# Optical_TX.net
KiCad netlist of a schematic drawn in Altium Designer
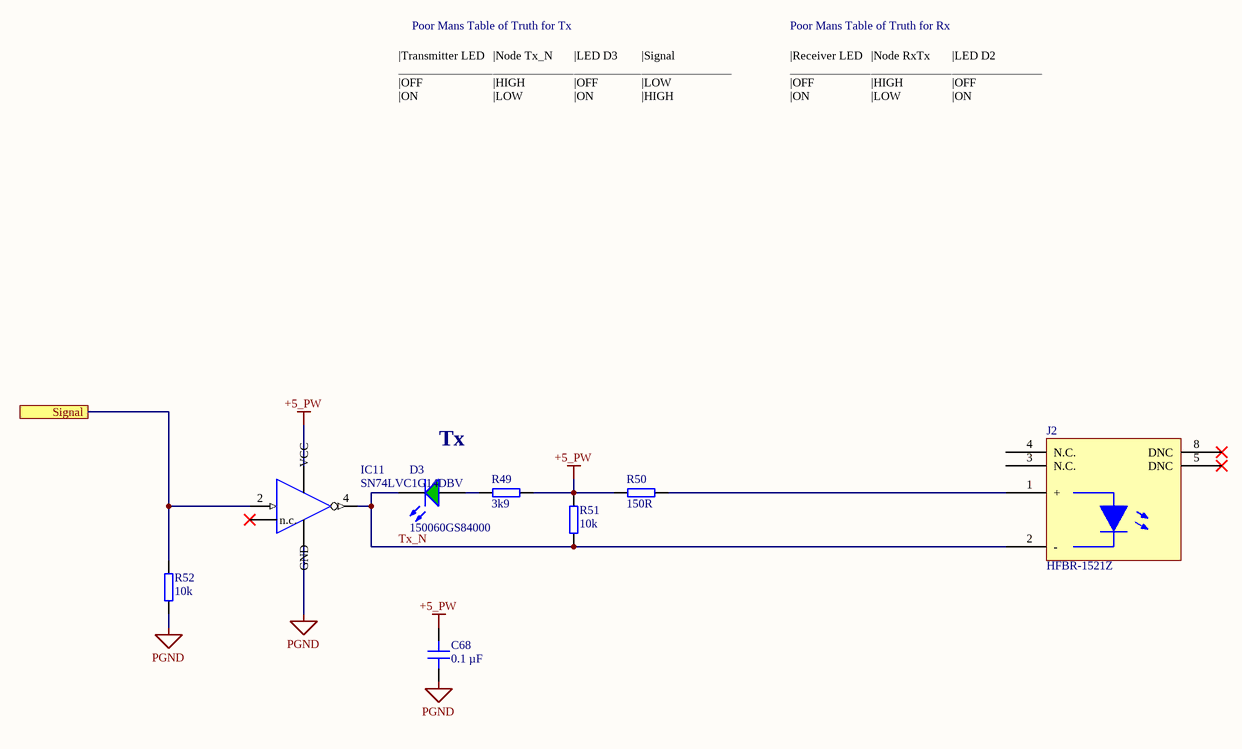
[diagram p0: Optical_TX.SchDoc]

(export (version "E")
  (design (tool "Eeschema 10.0.6"))
  (components
    (comp (ref "C68")
      (value "0.1 µF")
      (footprint "C_0603")
      (description "Capacitor 0603, 50 VDC, 0.1 µF, X7R")
      (fields
        (field (name "MANUFACTURER PART NUMBER") "C0603X104K5RAC7411")
        (field (name "MANUFACTURER") "KEMET")
        (field (name "CREATED FROM") "MGremer")
      )
      (libsource (lib "user") (part "Capacitor"))
    )
    (comp (ref "D3")
      (value "150060GS84000")
      (footprint "WL-SMCW_0603")
      (description "WL-SMCW SMD Mono-color Chip LED Waterclear Green")
      (fields (field (name "MANUFACTURER") "Wuerth Elektronik") (field (name "CREATED FROM") "MGremer"))
      (libsource (lib "user") (part "LED_Green"))
    )
    (comp (ref "IC11")
      (value "SN74LVC1G14DBV")
      (footprint "SOT23-5_L")
      (description "Inverting Schmitt trigger")
      (fields
        (field (name "MANUFACTURER") "Texas Instruments")
        (field (name "LCSC PART NUMBER") "C434069")
        (field (name "CREATED FROM") "VStarost")
      )
      (libsource (lib "user") (part "74AHCX1G14-5"))
    )
    (comp (ref "J2")
      (value "HFBR-1521Z")
      (footprint "HFBRx5XX")
      (description "Fibre Optic Transmitters, Link Horiz 5MBd Tx RoHS")
      (fields
        (field (name "MF") "Broadcom/Avago")
        (field (name "MANUFACTURER") "Broadcom")
        (field (name "CREATED") "2019_04_09_Kreppel")
        (field (name "CREATED FROM") "VStarost")
      )
      (libsource (lib "user") (part "HFBR-1521Z"))
    )
    (comp (ref "R49")
      (value "3k9")
      (footprint "RES 0603_1608")
      (description "SMD resistor E24 series")
      (fields
        (field (name "MANUFACTURER PART NUMBER") "RK73B1JTTDD392J")
        (field (name "MANUFACTURER") "KOA Speer")
        (field (name "CREATED FROM") "MGremer")
      )
      (libsource (lib "user") (part "Resistor"))
    )
    (comp (ref "R50")
      (value "150R")
      (footprint "RES 0603_1608")
      (description "SMD resistor E24 series")
      (fields
        (field (name "MANUFACTURER PART NUMBER") "RK73B1JTTD151J")
        (field (name "MANUFACTURER") "KOA Speer")
        (field (name "CREATED FROM") "MGremer")
      )
      (libsource (lib "user") (part "Resistor"))
    )
    (comp (ref "R51")
      (value "10k")
      (footprint "RES 0603_1608")
      (description "SMD resistor E24 series")
      (fields
        (field (name "MANUFACTURER PART NUMBER") "RK73B1JTTD103J")
        (field (name "MANUFACTURER") "KOA Speer")
        (field (name "CREATED FROM") "MGremer")
      )
      (libsource (lib "user") (part "Resistor"))
    )
    (comp (ref "R52")
      (value "10k")
      (footprint "RES 0603_1608")
      (description "SMD resistor E24 series")
      (fields
        (field (name "MANUFACTURER PART NUMBER") "RK73B1JTTD103J")
        (field (name "MANUFACTURER") "KOA Speer")
        (field (name "CREATED FROM") "MGremer")
      )
      (libsource (lib "user") (part "Resistor"))
    )
  )
  (nets
    (net (code "1") (name "+5_PW") (class "Default")
      (node (ref "C68") (pin "2") (pinfunction "2_2") (pintype "passive"))
      (node (ref "IC11") (pin "5") (pinfunction "VCC_5") (pintype "power_in"))
      (node (ref "R49") (pin "2") (pinfunction "2_2") (pintype "passive"))
      (node (ref "R50") (pin "1") (pinfunction "1_1") (pintype "passive"))
      (node (ref "R51") (pin "2") (pinfunction "2_2") (pintype "passive"))
    )
    (net (code "2") (name "/Signal") (class "Default")
      (node (ref "IC11") (pin "2") (pinfunction "A_2") (pintype "input"))
      (node (ref "R52") (pin "2") (pinfunction "2_2") (pintype "passive"))
    )
    (net (code "3") (name "/Tx_N") (class "Default")
      (node (ref "D3") (pin "1") (pinfunction "K_1") (pintype "passive"))
      (node (ref "IC11") (pin "4") (pinfunction "~{Y}_4") (pintype "output"))
      (node (ref "J2") (pin "2") (pinfunction "-_2") (pintype "passive"))
      (node (ref "R51") (pin "1") (pinfunction "1_1") (pintype "passive"))
    )
    (net (code "4") (name "Net-(D3-A)") (class "Default")
      (node (ref "D3") (pin "2") (pinfunction "A_2") (pintype "passive"))
      (node (ref "R49") (pin "1") (pinfunction "1_1") (pintype "passive"))
    )
    (net (code "5") (name "Net-(J2-+)") (class "Default")
      (node (ref "J2") (pin "1") (pinfunction "+_1") (pintype "passive"))
      (node (ref "R50") (pin "2") (pinfunction "2_2") (pintype "passive"))
    )
    (net (code "6") (name "PGND") (class "Default")
      (node (ref "C68") (pin "1") (pinfunction "1_1") (pintype "passive"))
      (node (ref "IC11") (pin "3") (pinfunction "GND_3") (pintype "power_in"))
      (node (ref "R52") (pin "1") (pinfunction "1_1") (pintype "passive"))
    )
    (net (code "7") (name "unconnected-(IC11-n.c.-Pad1)") (class "Default")
      (node (ref "IC11") (pin "1") (pinfunction "n.c._1") (pintype "passive+no_connect"))
    )
    (net (code "8") (name "unconnected-(J2-DNC-Pad5)") (class "Default")
      (node (ref "J2") (pin "5") (pinfunction "DNC_5") (pintype "passive+no_connect"))
    )
    (net (code "9") (name "unconnected-(J2-DNC-Pad8)") (class "Default")
      (node (ref "J2") (pin "8") (pinfunction "DNC_8") (pintype "passive+no_connect"))
    )
    (net (code "10") (name "unconnected-(J2-N.C.-Pad3)") (class "Default")
      (node (ref "J2") (pin "3") (pinfunction "N.C._3") (pintype "passive"))
    )
    (net (code "11") (name "unconnected-(J2-N.C.-Pad4)") (class "Default")
      (node (ref "J2") (pin "4") (pinfunction "N.C._4") (pintype "passive"))
    )
  )
)
